# NearBreakout.net
KiCad netlist of a schematic drawn in Altium Designer
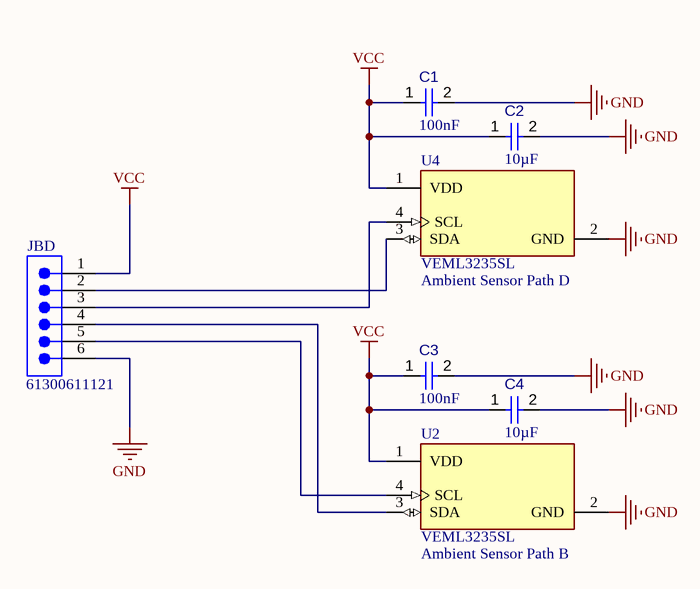
[diagram p0: NearBreakout.SchDoc]

(export (version "E")
  (design (tool "Eeschema 10.0.6"))
  (components
    (comp (ref "C1")
      (value "100nF")
      (footprint "FP-0805-L_2_01_0_2-W_1_25-IPC_B")
      (fields (field (name "Comment") "08051C104K4T2A"))
      (libsource (lib "University of Auckland") (part "CAP-NP-2"))
    )
    (comp (ref "C2")
      (value "10µF")
      (footprint "CAPC0805(2012)145_L")
      (description "Chip Capacitor, 10µF +/-20%, 25V, 0805, Thickness 1.45 mm")
      (fields (field (name "TOLERANCE") "10%") (field (name "Comment") "Capacitor 10µF +/-20% 25V 0805"))
      (libsource (lib "University of Auckland") (part "CAP-NP-2"))
    )
    (comp (ref "C3")
      (value "100nF")
      (footprint "FP-0805-L_2_01_0_2-W_1_25-IPC_B")
      (fields (field (name "Comment") "08051C104K4T2A"))
      (libsource (lib "University of Auckland") (part "CAP-NP-2"))
    )
    (comp (ref "C4")
      (value "10µF")
      (footprint "CAPC0805(2012)145_L")
      (description "Chip Capacitor, 10µF +/-20%, 25V, 0805, Thickness 1.45 mm")
      (fields (field (name "TOLERANCE") "10%") (field (name "Comment") "Capacitor 10µF +/-20% 25V 0805"))
      (libsource (lib "University of Auckland") (part "CAP-NP-2"))
    )
    (comp (ref "JBD")
      (value "61300611121")
      (footprint "61300611121")
      (libsource (lib "University of Auckland") (part "Header_Male_1R_06P"))
    )
    (comp (ref "U2")
      (value "VEML3235SL")
      (footprint "FP-VEML3235SL-MFG")
      (description "AMBIENT LIGHT SENSOR, IC, SIDE L")
      (libsource (lib "Altium Content Vault") (part "4813be54830ae130d2dc8c8f6975693"))
    )
    (comp (ref "U4")
      (value "VEML3235SL")
      (footprint "FP-VEML3235SL-MFG")
      (description "AMBIENT LIGHT SENSOR, IC, SIDE L")
      (libsource (lib "Altium Content Vault") (part "4813be54830ae130d2dc8c8f6975693"))
    )
  )
  (nets
    (net (code "1") (name "GND") (class "Default")
      (node (ref "C1") (pin "2") (pinfunction "2_2") (pintype "passive"))
      (node (ref "C2") (pin "2") (pinfunction "2_2") (pintype "passive"))
      (node (ref "C3") (pin "2") (pinfunction "2_2") (pintype "passive"))
      (node (ref "C4") (pin "2") (pinfunction "2_2") (pintype "passive"))
      (node (ref "JBD") (pin "6") (pinfunction "6_6") (pintype "passive"))
      (node (ref "U2") (pin "2") (pinfunction "GND_2") (pintype "power_in"))
      (node (ref "U4") (pin "2") (pinfunction "GND_2") (pintype "power_in"))
    )
    (net (code "2") (name "Net-(U2-SCL)") (class "Default")
      (node (ref "JBD") (pin "5") (pinfunction "5_5") (pintype "passive"))
      (node (ref "U2") (pin "4") (pinfunction "SCL_4") (pintype "input"))
    )
    (net (code "3") (name "Net-(U2-SDA)") (class "Default")
      (node (ref "JBD") (pin "4") (pinfunction "4_4") (pintype "passive"))
      (node (ref "U2") (pin "3") (pinfunction "SDA_3") (pintype "bidirectional"))
    )
    (net (code "4") (name "Net-(U4-SCL)") (class "Default")
      (node (ref "JBD") (pin "3") (pinfunction "3_3") (pintype "passive"))
      (node (ref "U4") (pin "4") (pinfunction "SCL_4") (pintype "input"))
    )
    (net (code "5") (name "Net-(U4-SDA)") (class "Default")
      (node (ref "JBD") (pin "2") (pinfunction "2_2") (pintype "passive"))
      (node (ref "U4") (pin "3") (pinfunction "SDA_3") (pintype "bidirectional"))
    )
    (net (code "6") (name "VCC") (class "Default")
      (node (ref "C1") (pin "1") (pinfunction "1_1") (pintype "passive"))
      (node (ref "C2") (pin "1") (pinfunction "1_1") (pintype "passive"))
      (node (ref "C3") (pin "1") (pinfunction "1_1") (pintype "passive"))
      (node (ref "C4") (pin "1") (pinfunction "1_1") (pintype "passive"))
      (node (ref "JBD") (pin "1") (pinfunction "1_1") (pintype "passive"))
      (node (ref "U2") (pin "1") (pinfunction "VDD_1") (pintype "power_in"))
      (node (ref "U4") (pin "1") (pinfunction "VDD_1") (pintype "power_in"))
    )
  )
)
